# DM1097_uSD.net
KiCad netlist of a schematic drawn in Altium Designer
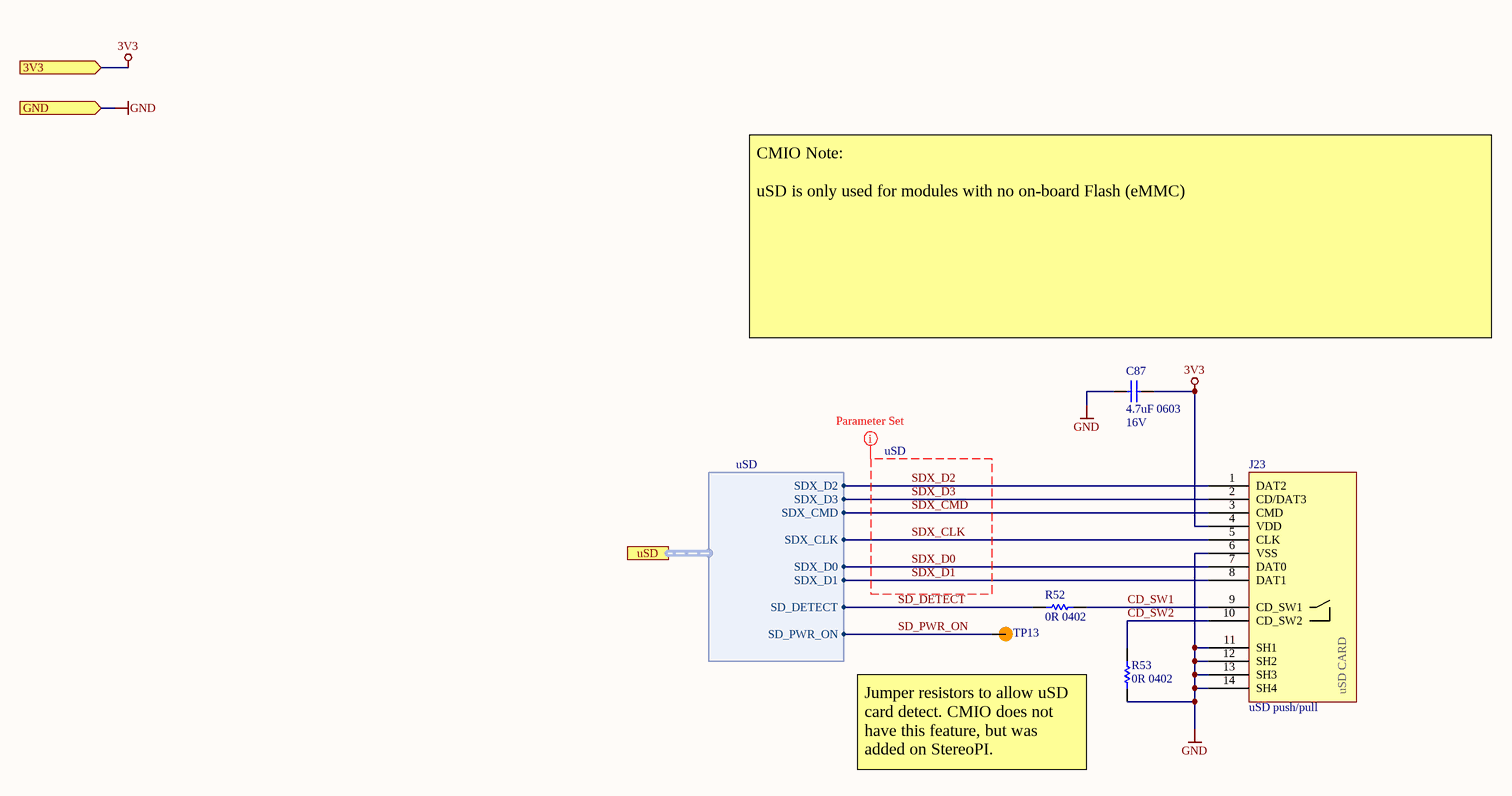
[diagram p0: DM1097_uSD.SchDoc]

(export (version "E")
  (design (tool "Eeschema 10.0.6"))
  (components
    (comp (ref "C87")
      (value "4.7uF 0603")
      (footprint "CAP_Altium_Vault_Generic:CAPC0603(1608)100_N")
      (description "CAP CER 4.7UF 16V X5R 0603 10%")
      (fields (field (name "TOLERANCE") "10%") (field (name "VOLTAGE RATING") "16V"))
      (libsource (lib "LuxonisMaster") (part "GRM188R61C475KAAJD"))
    )
    (comp (ref "J23")
      (value "uSD push/pull")
      (footprint "LuxonisMaster:104031-0811")
      (description "CONN MICRO SD CARD PUSH-PULL R/A")
      (libsource (lib "LuxonisMaster") (part "104031-0811"))
    )
    (comp (ref "R52")
      (value "0R 0402")
      (footprint "RES_Altium_Vault_Generic:RESC0402(1005)_N")
      (description "RES SMD 0 OHM JUMPER 1/16W 0402")
      (fields (field (name "TOLERANCE") "5%"))
      (libsource (lib "LuxonisMaster") (part "CRCW04020000Z0ED"))
    )
    (comp (ref "R53")
      (value "0R 0402")
      (footprint "RES_Altium_Vault_Generic:RESC0402(1005)_N")
      (description "RES SMD 0 OHM JUMPER 1/16W 0402")
      (fields (field (name "TOLERANCE") "5%"))
      (libsource (lib "LuxonisMaster") (part "CRCW04020000Z0ED"))
    )
    (comp (ref "TP13")
      (value "TP100_200_NS")
      (footprint "LuxonisMaster:TP100_200_NS")
      (libsource (lib "LuxonisMaster") (part "TEST_POINT"))
    )
  )
  (nets
    (net (code "2") (name "/CD_SW1") (class "Default")
      (node (ref "J23") (pin "9") (pinfunction "CD_SW1_9") (pintype "passive"))
      (node (ref "R52") (pin "1") (pinfunction "1_1") (pintype "passive"))
    )
    (net (code "3") (name "/CD_SW2") (class "Default")
      (node (ref "J23") (pin "10") (pinfunction "CD_SW2_10") (pintype "passive"))
      (node (ref "R53") (pin "2") (pinfunction "2_2") (pintype "passive"))
    )
    (net (code "4") (name "/SDX_CLK") (class "Default")
      (node (ref "J23") (pin "5") (pinfunction "CLK_5") (pintype "passive"))
    )
    (net (code "5") (name "/SDX_CMD") (class "Default")
      (node (ref "J23") (pin "3") (pinfunction "CMD_3") (pintype "passive"))
    )
    (net (code "6") (name "/SDX_D0") (class "Default")
      (node (ref "J23") (pin "7") (pinfunction "DAT0_7") (pintype "passive"))
    )
    (net (code "7") (name "/SDX_D1") (class "Default")
      (node (ref "J23") (pin "8") (pinfunction "DAT1_8") (pintype "passive"))
    )
    (net (code "8") (name "/SDX_D2") (class "Default")
      (node (ref "J23") (pin "1") (pinfunction "DAT2_1") (pintype "passive"))
    )
    (net (code "9") (name "/SDX_D3") (class "Default")
      (node (ref "J23") (pin "2") (pinfunction "CD/DAT3_2") (pintype "passive"))
    )
    (net (code "10") (name "/SD_DETECT") (class "Default")
      (node (ref "R52") (pin "2") (pinfunction "2_2") (pintype "passive"))
    )
    (net (code "11") (name "/SD_PWR_ON") (class "Default") (node (ref "TP13") (pin "1") (pintype "passive")))
    (net (code "13") (name "3V3") (class "Default")
      (node (ref "C87") (pin "2") (pinfunction "2_2") (pintype "passive"))
      (node (ref "J23") (pin "4") (pinfunction "VDD_4") (pintype "passive"))
    )
    (net (code "14") (name "GND") (class "Default")
      (node (ref "C87") (pin "1") (pinfunction "1_1") (pintype "passive"))
      (node (ref "J23") (pin "11") (pinfunction "SH1_11") (pintype "passive"))
      (node (ref "J23") (pin "12") (pinfunction "SH2_12") (pintype "passive"))
      (node (ref "J23") (pin "13") (pinfunction "SH3_13") (pintype "passive"))
      (node (ref "J23") (pin "14") (pinfunction "SH4_14") (pintype "passive"))
      (node (ref "J23") (pin "6") (pinfunction "VSS_6") (pintype "passive"))
      (node (ref "R53") (pin "1") (pinfunction "1_1") (pintype "passive"))
    )
  )
)
